# SSB_Transceiver_Crystal_Ladder_Filter.net
KiCad netlist of a schematic drawn in EAGLE
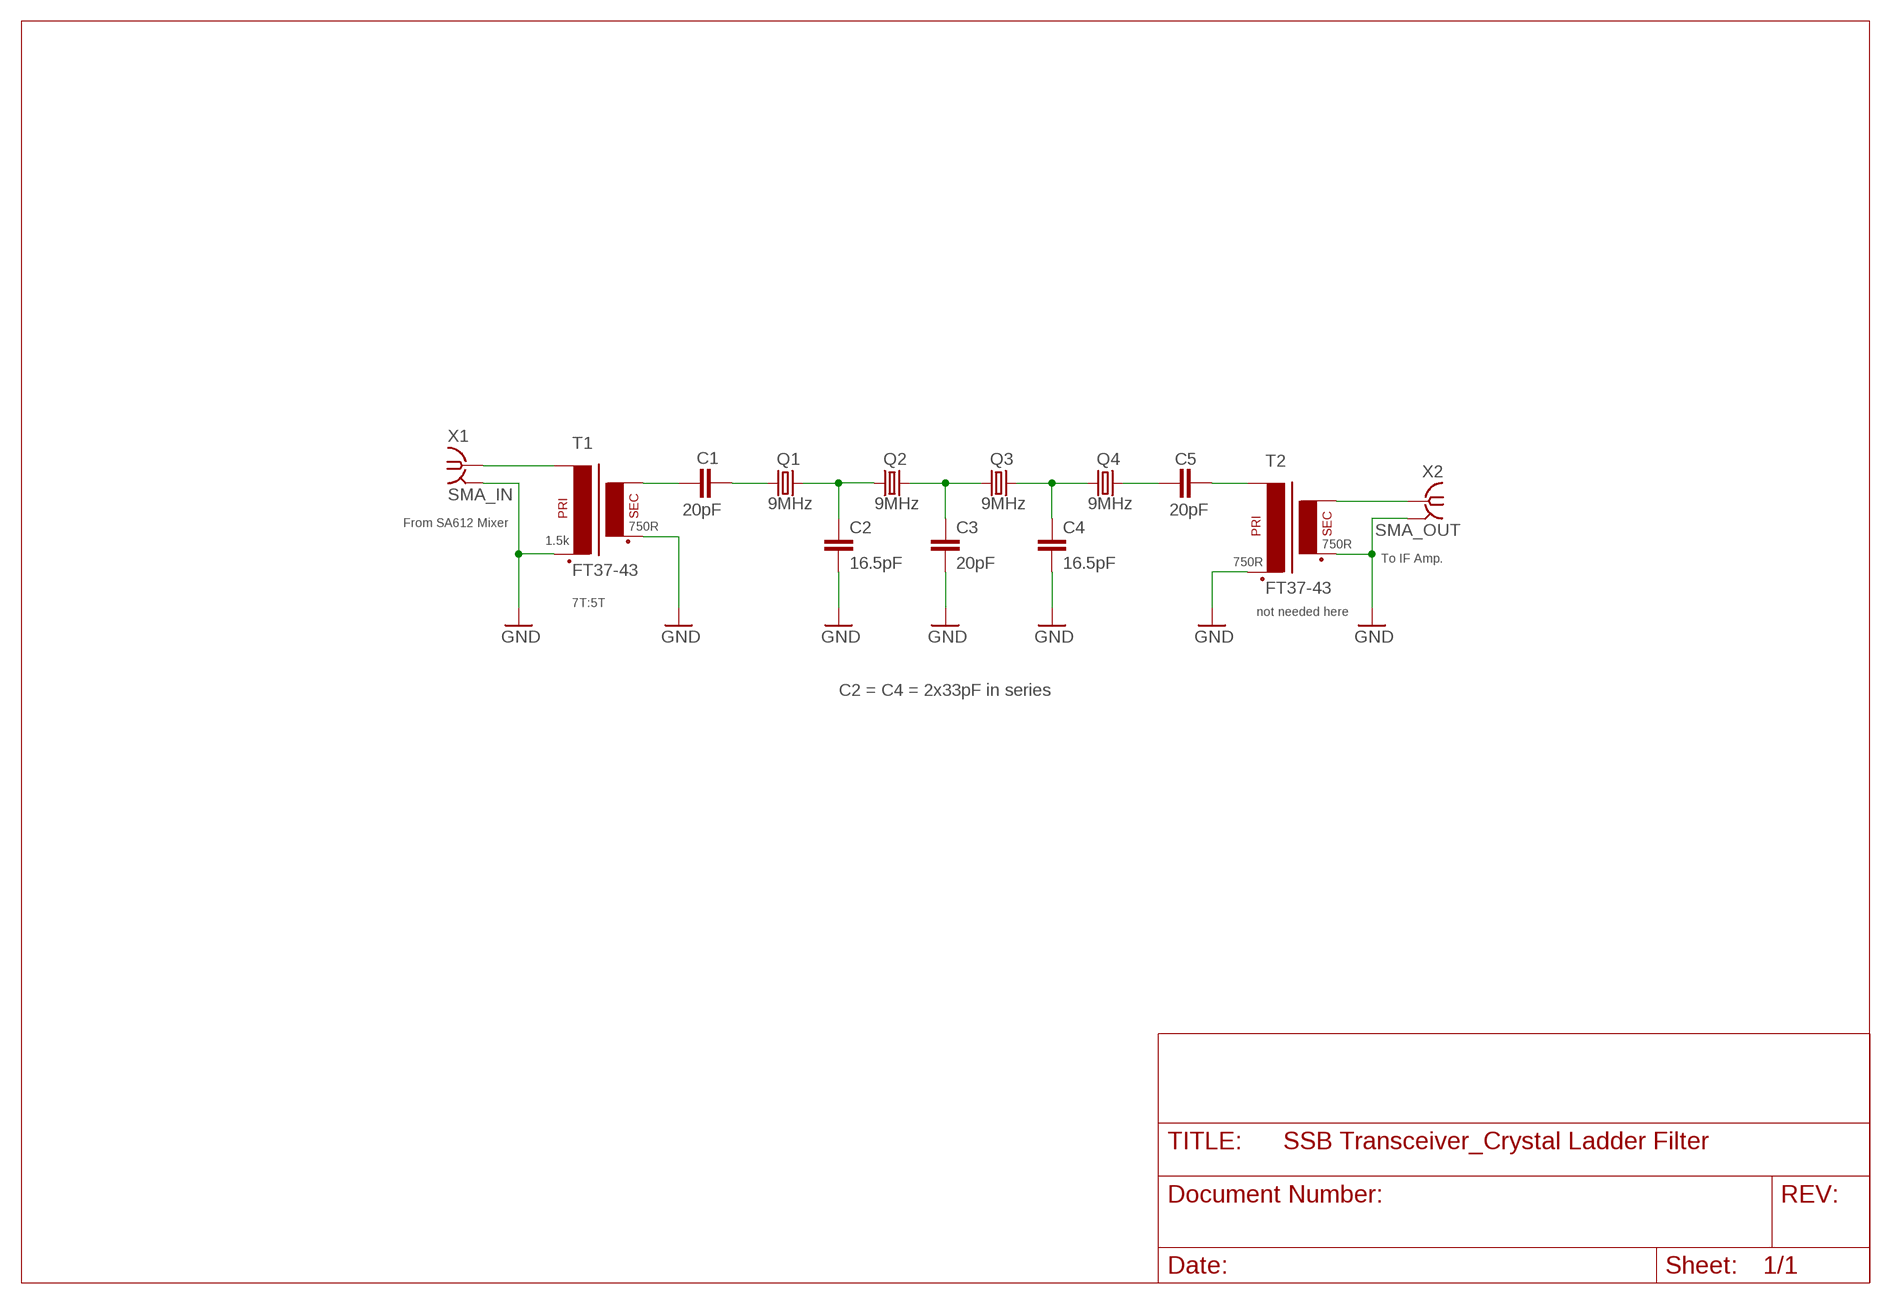
[diagram p0: schematic, sheet 1]

(export (version "E")
  (design (tool "Eeschema 10.0.6"))
  (components
    (comp (ref "C1")
      (value "20pF")
      (footprint "eagle-import:C0805")
      (libsource (lib "eagle-import") (part "C-EUC0805"))
    )
    (comp (ref "C2")
      (value "16.5pF")
      (footprint "eagle-import:C0805")
      (libsource (lib "eagle-import") (part "C-EUC0805"))
    )
    (comp (ref "C3")
      (value "20pF")
      (footprint "eagle-import:C0805")
      (libsource (lib "eagle-import") (part "C-EUC0805"))
    )
    (comp (ref "C4")
      (value "16.5pF")
      (footprint "eagle-import:C0805")
      (libsource (lib "eagle-import") (part "C-EUC0805"))
    )
    (comp (ref "C5")
      (value "20pF")
      (footprint "eagle-import:C0805")
      (libsource (lib "eagle-import") (part "C-EUC0805"))
    )
    (comp (ref "Q1")
      (value "9MHz")
      (footprint "eagle-import:HC49_S")
      (libsource (lib "eagle-import") (part "CRYSTALHC49S"))
    )
    (comp (ref "Q2")
      (value "9MHz")
      (footprint "eagle-import:HC49_S")
      (libsource (lib "eagle-import") (part "CRYSTALHC49S"))
    )
    (comp (ref "Q3")
      (value "9MHz")
      (footprint "eagle-import:HC49_S")
      (libsource (lib "eagle-import") (part "CRYSTALHC49S"))
    )
    (comp (ref "Q4")
      (value "9MHz")
      (footprint "eagle-import:HC49_S")
      (libsource (lib "eagle-import") (part "CRYSTALHC49S"))
    )
    (comp (ref "T1")
      (value "FT37-43")
      (footprint "eagle-import:FT37-43SMD")
      (libsource (lib "eagle-import") (part "FT37-43"))
    )
    (comp (ref "T2")
      (value "FT37-43")
      (footprint "eagle-import:FT37-43SMD")
      (libsource (lib "eagle-import") (part "FT37-43"))
    )
    (comp (ref "X1")
      (value "SMA_IN")
      (footprint "eagle-import:J502-ND-142-0711-821_826")
      (fields (field (name "MF") "JOHNSON COMPONENTS") (field (name "MPN") "142-0711-821"))
      (libsource (lib "eagle-import") (part "SMA-142-0711-821/826"))
    )
    (comp (ref "X2")
      (value "SMA_OUT")
      (footprint "eagle-import:J502-ND-142-0711-821_826")
      (fields (field (name "MF") "JOHNSON COMPONENTS") (field (name "MPN") "142-0711-821"))
      (libsource (lib "eagle-import") (part "SMA-142-0711-821/826"))
    )
  )
  (nets
    (net (code "1") (name "GND") (class "Default")
      (node (ref "C2") (pin "2") (pinfunction "2_2") (pintype "passive"))
      (node (ref "C3") (pin "2") (pinfunction "2_2") (pintype "passive"))
      (node (ref "C4") (pin "2") (pinfunction "2_2") (pintype "passive"))
      (node (ref "T1") (pin "P$2") (pinfunction "P2_P$2") (pintype "passive"))
      (node (ref "T1") (pin "S$2") (pinfunction "S2_S$2") (pintype "passive"))
      (node (ref "T2") (pin "P$2") (pinfunction "P2_P$2") (pintype "passive"))
      (node (ref "T2") (pin "S$2") (pinfunction "S2_S$2") (pintype "passive"))
      (node (ref "X1") (pin "G@1") (pinfunction "2_G@1") (pintype "passive"))
      (node (ref "X1") (pin "G@2") (pinfunction "2_G@2") (pintype "passive"))
      (node (ref "X1") (pin "G@3") (pinfunction "2_G@3") (pintype "passive"))
      (node (ref "X1") (pin "G@4") (pinfunction "2_G@4") (pintype "passive"))
      (node (ref "X2") (pin "G@1") (pinfunction "2_G@1") (pintype "passive"))
      (node (ref "X2") (pin "G@2") (pinfunction "2_G@2") (pintype "passive"))
      (node (ref "X2") (pin "G@3") (pinfunction "2_G@3") (pintype "passive"))
      (node (ref "X2") (pin "G@4") (pinfunction "2_G@4") (pintype "passive"))
    )
    (net (code "2") (name "Net-(C1-Pad2)") (class "Default")
      (node (ref "C1") (pin "2") (pinfunction "2_2") (pintype "passive"))
      (node (ref "Q1") (pin "1") (pinfunction "1_1") (pintype "passive"))
    )
    (net (code "3") (name "Net-(C2-Pad1)") (class "Default")
      (node (ref "C2") (pin "1") (pinfunction "1_1") (pintype "passive"))
      (node (ref "Q1") (pin "2") (pinfunction "2_2") (pintype "passive"))
      (node (ref "Q2") (pin "1") (pinfunction "1_1") (pintype "passive"))
    )
    (net (code "4") (name "Net-(C3-Pad1)") (class "Default")
      (node (ref "C3") (pin "1") (pinfunction "1_1") (pintype "passive"))
      (node (ref "Q2") (pin "2") (pinfunction "2_2") (pintype "passive"))
      (node (ref "Q3") (pin "1") (pinfunction "1_1") (pintype "passive"))
    )
    (net (code "5") (name "Net-(C4-Pad1)") (class "Default")
      (node (ref "C4") (pin "1") (pinfunction "1_1") (pintype "passive"))
      (node (ref "Q3") (pin "2") (pinfunction "2_2") (pintype "passive"))
      (node (ref "Q4") (pin "1") (pinfunction "1_1") (pintype "passive"))
    )
    (net (code "6") (name "Net-(C5-Pad1)") (class "Default")
      (node (ref "C5") (pin "1") (pinfunction "1_1") (pintype "passive"))
      (node (ref "Q4") (pin "2") (pinfunction "2_2") (pintype "passive"))
    )
    (net (code "7") (name "Net-(T1-P1)") (class "Default")
      (node (ref "T1") (pin "P$1") (pinfunction "P1_P$1") (pintype "passive"))
      (node (ref "X1") (pin "1") (pinfunction "1_1") (pintype "passive"))
    )
    (net (code "8") (name "Net-(T1-S1)") (class "Default")
      (node (ref "C1") (pin "1") (pinfunction "1_1") (pintype "passive"))
      (node (ref "T1") (pin "S$1") (pinfunction "S1_S$1") (pintype "passive"))
    )
    (net (code "9") (name "Net-(T2-P1)") (class "Default")
      (node (ref "C5") (pin "2") (pinfunction "2_2") (pintype "passive"))
      (node (ref "T2") (pin "P$1") (pinfunction "P1_P$1") (pintype "passive"))
    )
    (net (code "10") (name "Net-(T2-S1)") (class "Default")
      (node (ref "T2") (pin "S$1") (pinfunction "S1_S$1") (pintype "passive"))
      (node (ref "X2") (pin "1") (pinfunction "1_1") (pintype "passive"))
    )
  )
)
